# Buffer.net
KiCad netlist of a schematic drawn in Altium Designer
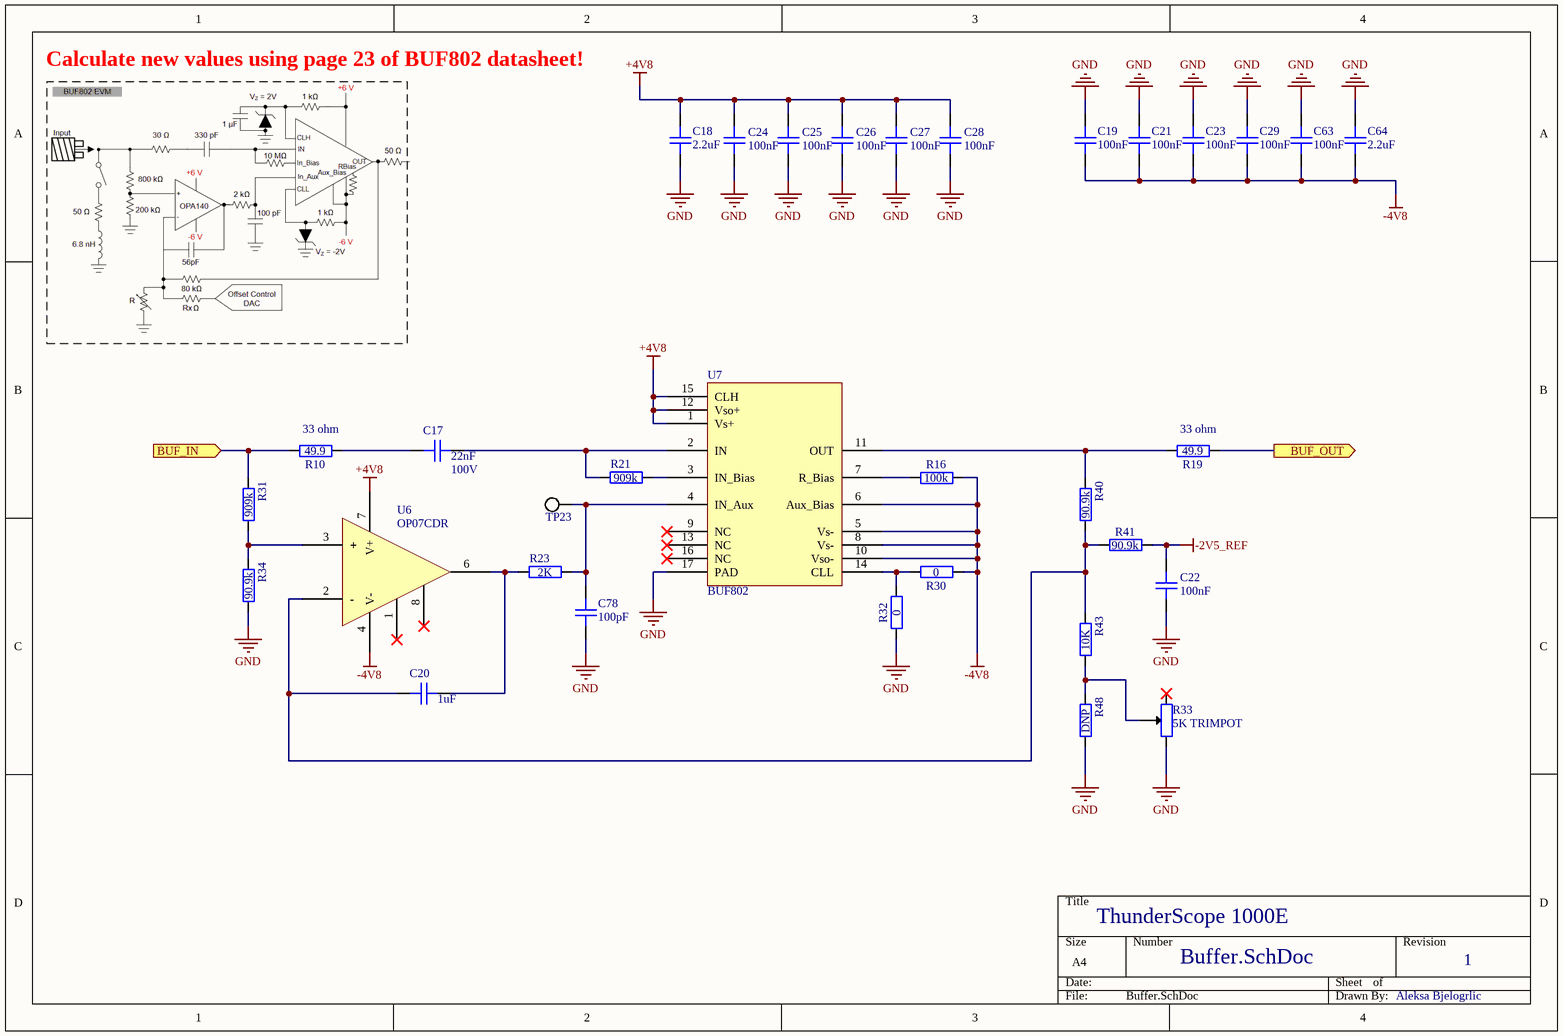
[diagram p0: Buffer.SchDoc]

(export (version "E")
  (design (tool "Eeschema 10.0.6"))
  (components
    (comp (ref "C17")
      (value "22nF")
      (footprint "GEN_C_0603")
      (fields (field (name "VOLTAGE RATING") "100V"))
      (libsource (lib "DSO") (part "CAP 22nF 100V X7R 0603"))
    )
    (comp (ref "C18")
      (value "2.2uF")
      (footprint "GEN_C_0402")
      (libsource (lib "DSO") (part "CAP 2.2uF 10V X5R 0402"))
    )
    (comp (ref "C19")
      (value "100nF")
      (footprint "GEN_C_0402")
      (libsource (lib "DSO") (part "CAP 100nF 16V X7R 0402"))
    )
    (comp (ref "C20")
      (value "1uF")
      (footprint "GEN_C_0402")
      (libsource (lib "DSO") (part "CAP 1uF 25V X5R 0402"))
    )
    (comp (ref "C21")
      (value "100nF")
      (footprint "GEN_C_0402")
      (libsource (lib "DSO") (part "CAP 100nF 16V X7R 0402"))
    )
    (comp (ref "C22")
      (value "100nF")
      (footprint "GEN_C_0402")
      (libsource (lib "DSO") (part "CAP 100nF 16V X7R 0402"))
    )
    (comp (ref "C23")
      (value "100nF")
      (footprint "GEN_C_0402")
      (libsource (lib "DSO") (part "CAP 100nF 16V X7R 0402"))
    )
    (comp (ref "C24")
      (value "100nF")
      (footprint "GEN_C_0402")
      (libsource (lib "DSO") (part "CAP 100nF 16V X7R 0402"))
    )
    (comp (ref "C25")
      (value "100nF")
      (footprint "GEN_C_0402")
      (libsource (lib "DSO") (part "CAP 100nF 16V X7R 0402"))
    )
    (comp (ref "C26")
      (value "100nF")
      (footprint "GEN_C_0402")
      (libsource (lib "DSO") (part "CAP 100nF 16V X7R 0402"))
    )
    (comp (ref "C27")
      (value "100nF")
      (footprint "GEN_C_0402")
      (libsource (lib "DSO") (part "CAP 100nF 16V X7R 0402"))
    )
    (comp (ref "C28")
      (value "100nF")
      (footprint "GEN_C_0402")
      (libsource (lib "DSO") (part "CAP 100nF 16V X7R 0402"))
    )
    (comp (ref "C29")
      (value "100nF")
      (footprint "GEN_C_0402")
      (libsource (lib "DSO") (part "CAP 100nF 16V X7R 0402"))
    )
    (comp (ref "C63")
      (value "100nF")
      (footprint "GEN_C_0402")
      (libsource (lib "DSO") (part "CAP 100nF 16V X7R 0402"))
    )
    (comp (ref "C64")
      (value "2.2uF")
      (footprint "GEN_C_0402")
      (libsource (lib "DSO") (part "CAP 2.2uF 10V X5R 0402"))
    )
    (comp (ref "C78")
      (value "100pF")
      (footprint "GEN_C_0402")
      (libsource (lib "DSO") (part "CAP 100pF 50V C0G 0402"))
    )
    (comp (ref "R10")
      (value "49.9")
      (footprint "GEN_R_0402")
      (fields (field (name "TOLERANCE") "1%"))
      (libsource (lib "DSO") (part "RES 49.9 OHM 1% 1/10W 0402"))
    )
    (comp (ref "R16")
      (value "100k")
      (footprint "GEN_R_0402")
      (fields (field (name "TOLERANCE") "1%"))
      (libsource (lib "DSO") (part "RES 100K OHM 1% 1/10W 0402"))
    )
    (comp (ref "R19")
      (value "49.9")
      (footprint "GEN_R_0402")
      (fields (field (name "TOLERANCE") "1%"))
      (libsource (lib "DSO") (part "RES 49.9 OHM 1% 1/10W 0402"))
    )
    (comp (ref "R21")
      (value "909k")
      (footprint "GEN_R_0402")
      (fields (field (name "TOLERANCE") "1%"))
      (libsource (lib "DSO") (part "RES 909K OHM 1% 1/16W 0402"))
    )
    (comp (ref "R23")
      (value "2K")
      (footprint "GEN_R_0402")
      (fields (field (name "TOLERANCE") "1%"))
      (libsource (lib "DSO") (part "RES 2K OHM 1% 1/16W 0402"))
    )
    (comp (ref "R30")
      (value "0")
      (footprint "GEN_R_0402")
      (libsource (lib "DSO") (part "RES 0 OHM 1/16W 0402"))
    )
    (comp (ref "R31")
      (value "909k")
      (footprint "GEN_R_0402")
      (fields (field (name "TOLERANCE") "1%"))
      (libsource (lib "") (part "RES 909K OHM 1% 1/16W 0402_1"))
    )
    (comp (ref "R32")
      (value "0")
      (footprint "GEN_R_0402")
      (libsource (lib "") (part "RES 0 OHM 1/16W 0402_1"))
    )
    (comp (ref "R33")
      (value "5K TRIMPOT")
      (footprint "BOU_3mm_POT")
      (fields (field (name "TOLERANCE") "1%"))
      (libsource (lib "DSO") (part "TRIMMER 5K OHM 0.1W J LEAD TOP"))
    )
    (comp (ref "R34")
      (value "90.9k")
      (footprint "GEN_R_0402")
      (fields (field (name "TOLERANCE") "1%"))
      (libsource (lib "") (part "RES 90.9K OHM 1% 1/16W 0402_1"))
    )
    (comp (ref "R40")
      (value "90.9k")
      (footprint "GEN_R_0402")
      (fields (field (name "TOLERANCE") "1%"))
      (libsource (lib "") (part "RES 90.9K OHM 1% 1/16W 0402_1"))
    )
    (comp (ref "R41")
      (value "90.9k")
      (footprint "GEN_R_0402")
      (fields (field (name "TOLERANCE") "1%"))
      (libsource (lib "DSO") (part "RES 90.9K OHM 1% 1/16W 0402"))
    )
    (comp (ref "R43")
      (value "10K")
      (footprint "GEN_R_0402")
      (fields (field (name "TOLERANCE") "1%"))
      (libsource (lib "DSO") (part "RES 10K OHM 1% 1/10W 0402"))
    )
    (comp (ref "R48")
      (value "DNP")
      (footprint "GEN_R_0402")
      (fields (field (name "TOLERANCE") "1%"))
      (libsource (lib "DSO") (part "RES DNP 0402"))
    )
    (comp (ref "TP23") (value "PCB") (footprint "GEN_TP_PCB") (libsource (lib "DSO") (part "TP PCB 1mm")))
    (comp (ref "U6")
      (value "OP07CDR")
      (footprint "TI_SOIC8_D0008A")
      (libsource (lib "DSO") (part "IC OPAMP OP07CDR"))
    )
    (comp (ref "U7")
      (value "BUF802")
      (footprint "TI_VQFN_RGT0016C")
      (libsource (lib "DSO") (part "IC BUFFER AMP BUF802"))
    )
  )
  (nets
    (net (code "1") (name "+4V8") (class "Default")
      (node (ref "C18") (pin "2") (pinfunction "2_2") (pintype "passive"))
      (node (ref "C24") (pin "1") (pinfunction "1_1") (pintype "passive"))
      (node (ref "C25") (pin "1") (pinfunction "1_1") (pintype "passive"))
      (node (ref "C26") (pin "1") (pinfunction "1_1") (pintype "passive"))
      (node (ref "C27") (pin "2") (pinfunction "2_2") (pintype "passive"))
      (node (ref "C28") (pin "2") (pinfunction "2_2") (pintype "passive"))
      (node (ref "U6") (pin "7") (pinfunction "V+_7") (pintype "passive"))
      (node (ref "U7") (pin "1") (pinfunction "Vs+_1") (pintype "passive"))
      (node (ref "U7") (pin "12") (pinfunction "Vso+_12") (pintype "passive"))
      (node (ref "U7") (pin "15") (pinfunction "CLH_15") (pintype "passive"))
    )
    (net (code "2") (name "-2V5_REF") (class "Default")
      (node (ref "C22") (pin "1") (pinfunction "1_1") (pintype "passive"))
      (node (ref "R41") (pin "1") (pinfunction "1_1") (pintype "passive"))
    )
    (net (code "3") (name "-4V8") (class "Default")
      (node (ref "C19") (pin "2") (pinfunction "2_2") (pintype "passive"))
      (node (ref "C21") (pin "2") (pinfunction "2_2") (pintype "passive"))
      (node (ref "C23") (pin "1") (pinfunction "1_1") (pintype "passive"))
      (node (ref "C29") (pin "1") (pinfunction "1_1") (pintype "passive"))
      (node (ref "C63") (pin "1") (pinfunction "1_1") (pintype "passive"))
      (node (ref "C64") (pin "2") (pinfunction "2_2") (pintype "passive"))
      (node (ref "R16") (pin "2") (pinfunction "2_2") (pintype "passive"))
      (node (ref "R30") (pin "1") (pinfunction "1_1") (pintype "passive"))
      (node (ref "U6") (pin "4") (pinfunction "V-_4") (pintype "passive"))
      (node (ref "U7") (pin "10") (pinfunction "Vso-_10") (pintype "passive"))
      (node (ref "U7") (pin "5") (pinfunction "Vs-_5") (pintype "passive"))
      (node (ref "U7") (pin "6") (pinfunction "Aux_Bias_6") (pintype "passive"))
      (node (ref "U7") (pin "8") (pinfunction "Vs-_8") (pintype "passive"))
    )
    (net (code "4") (name "/BUF_IN") (class "Default")
      (node (ref "R10") (pin "1") (pinfunction "1_1") (pintype "passive"))
      (node (ref "R31") (pin "2") (pinfunction "2_2") (pintype "passive"))
    )
    (net (code "5") (name "/BUF_OUT") (class "Default")
      (node (ref "R19") (pin "2") (pinfunction "2_2") (pintype "passive"))
    )
    (net (code "6") (name "GND") (class "Default")
      (node (ref "C18") (pin "1") (pinfunction "1_1") (pintype "passive"))
      (node (ref "C19") (pin "1") (pinfunction "1_1") (pintype "passive"))
      (node (ref "C21") (pin "1") (pinfunction "1_1") (pintype "passive"))
      (node (ref "C22") (pin "2") (pinfunction "2_2") (pintype "passive"))
      (node (ref "C23") (pin "2") (pinfunction "2_2") (pintype "passive"))
      (node (ref "C24") (pin "2") (pinfunction "2_2") (pintype "passive"))
      (node (ref "C25") (pin "2") (pinfunction "2_2") (pintype "passive"))
      (node (ref "C26") (pin "2") (pinfunction "2_2") (pintype "passive"))
      (node (ref "C27") (pin "1") (pinfunction "1_1") (pintype "passive"))
      (node (ref "C28") (pin "1") (pinfunction "1_1") (pintype "passive"))
      (node (ref "C29") (pin "2") (pinfunction "2_2") (pintype "passive"))
      (node (ref "C63") (pin "2") (pinfunction "2_2") (pintype "passive"))
      (node (ref "C64") (pin "1") (pinfunction "1_1") (pintype "passive"))
      (node (ref "C78") (pin "1") (pinfunction "1_1") (pintype "passive"))
      (node (ref "R32") (pin "1") (pinfunction "1_1") (pintype "passive"))
      (node (ref "R33") (pin "3") (pinfunction "3_3") (pintype "passive"))
      (node (ref "R34") (pin "1") (pinfunction "1_1") (pintype "passive"))
      (node (ref "R48") (pin "1") (pinfunction "1_1") (pintype "passive"))
      (node (ref "U7") (pin "17") (pinfunction "PAD_17") (pintype "passive"))
    )
    (net (code "7") (name "Net-(C17-Pad2)") (class "Default")
      (node (ref "C17") (pin "2") (pinfunction "2_2") (pintype "passive"))
      (node (ref "R10") (pin "2") (pinfunction "2_2") (pintype "passive"))
    )
    (net (code "8") (name "Net-(R33-Pad2)") (class "Default")
      (node (ref "R33") (pin "2") (pinfunction "2_2") (pintype "passive"))
      (node (ref "R43") (pin "1") (pinfunction "1_1") (pintype "passive"))
      (node (ref "R48") (pin "2") (pinfunction "2_2") (pintype "passive"))
    )
    (net (code "9") (name "Net-(U6-+)") (class "Default")
      (node (ref "R31") (pin "1") (pinfunction "1_1") (pintype "passive"))
      (node (ref "R34") (pin "2") (pinfunction "2_2") (pintype "passive"))
      (node (ref "U6") (pin "3") (pinfunction "+_3") (pintype "passive"))
    )
    (net (code "10") (name "Net-(U6--)") (class "Default")
      (node (ref "C20") (pin "2") (pinfunction "2_2") (pintype "passive"))
      (node (ref "R40") (pin "1") (pinfunction "1_1") (pintype "passive"))
      (node (ref "R41") (pin "2") (pinfunction "2_2") (pintype "passive"))
      (node (ref "R43") (pin "2") (pinfunction "2_2") (pintype "passive"))
      (node (ref "U6") (pin "2") (pinfunction "-_2") (pintype "passive"))
    )
    (net (code "11") (name "Net-(U6-OUT)") (class "Default")
      (node (ref "C20") (pin "1") (pinfunction "1_1") (pintype "passive"))
      (node (ref "R23") (pin "2") (pinfunction "2_2") (pintype "passive"))
      (node (ref "U6") (pin "6") (pinfunction "OUT_6") (pintype "passive"))
    )
    (net (code "12") (name "Net-(U7-CLL)") (class "Default")
      (node (ref "R30") (pin "2") (pinfunction "2_2") (pintype "passive"))
      (node (ref "R32") (pin "2") (pinfunction "2_2") (pintype "passive"))
      (node (ref "U7") (pin "14") (pinfunction "CLL_14") (pintype "passive"))
    )
    (net (code "13") (name "Net-(U7-IN)") (class "Default")
      (node (ref "C17") (pin "1") (pinfunction "1_1") (pintype "passive"))
      (node (ref "R21") (pin "2") (pinfunction "2_2") (pintype "passive"))
      (node (ref "U7") (pin "2") (pinfunction "IN_2") (pintype "passive"))
    )
    (net (code "14") (name "Net-(U7-IN_Aux)") (class "Default")
      (node (ref "C78") (pin "2") (pinfunction "2_2") (pintype "passive"))
      (node (ref "R23") (pin "1") (pinfunction "1_1") (pintype "passive"))
      (node (ref "TP23") (pin "1") (pinfunction "1_1") (pintype "passive"))
      (node (ref "U7") (pin "4") (pinfunction "IN_Aux_4") (pintype "passive"))
    )
    (net (code "15") (name "Net-(U7-IN_Bias)") (class "Default")
      (node (ref "R21") (pin "1") (pinfunction "1_1") (pintype "passive"))
      (node (ref "U7") (pin "3") (pinfunction "IN_Bias_3") (pintype "passive"))
    )
    (net (code "16") (name "Net-(U7-OUT)") (class "Default")
      (node (ref "R19") (pin "1") (pinfunction "1_1") (pintype "passive"))
      (node (ref "R40") (pin "2") (pinfunction "2_2") (pintype "passive"))
      (node (ref "U7") (pin "11") (pinfunction "OUT_11") (pintype "passive"))
    )
    (net (code "17") (name "Net-(U7-R_Bias)") (class "Default")
      (node (ref "R16") (pin "1") (pinfunction "1_1") (pintype "passive"))
      (node (ref "U7") (pin "7") (pinfunction "R_Bias_7") (pintype "passive"))
    )
    (net (code "18") (name "unconnected-(R33-Pad1)") (class "Default")
      (node (ref "R33") (pin "1") (pinfunction "1_1") (pintype "passive+no_connect"))
    )
    (net (code "19") (name "unconnected-(U6-N1-Pad1)") (class "Default")
      (node (ref "U6") (pin "1") (pinfunction "N1_1") (pintype "passive+no_connect"))
    )
    (net (code "20") (name "unconnected-(U6-N2-Pad8)") (class "Default")
      (node (ref "U6") (pin "8") (pinfunction "N2_8") (pintype "passive+no_connect"))
    )
    (net (code "21") (name "unconnected-(U7-NC-Pad9)") (class "Default")
      (node (ref "U7") (pin "9") (pinfunction "NC_9") (pintype "passive+no_connect"))
    )
    (net (code "22") (name "unconnected-(U7-NC-Pad13)") (class "Default")
      (node (ref "U7") (pin "13") (pinfunction "NC_13") (pintype "passive+no_connect"))
    )
    (net (code "23") (name "unconnected-(U7-NC-Pad16)") (class "Default")
      (node (ref "U7") (pin "16") (pinfunction "NC_16") (pintype "passive+no_connect"))
    )
  )
)
